# uChameleon.net
KiCad netlist of a schematic drawn in EasyEDA Pro
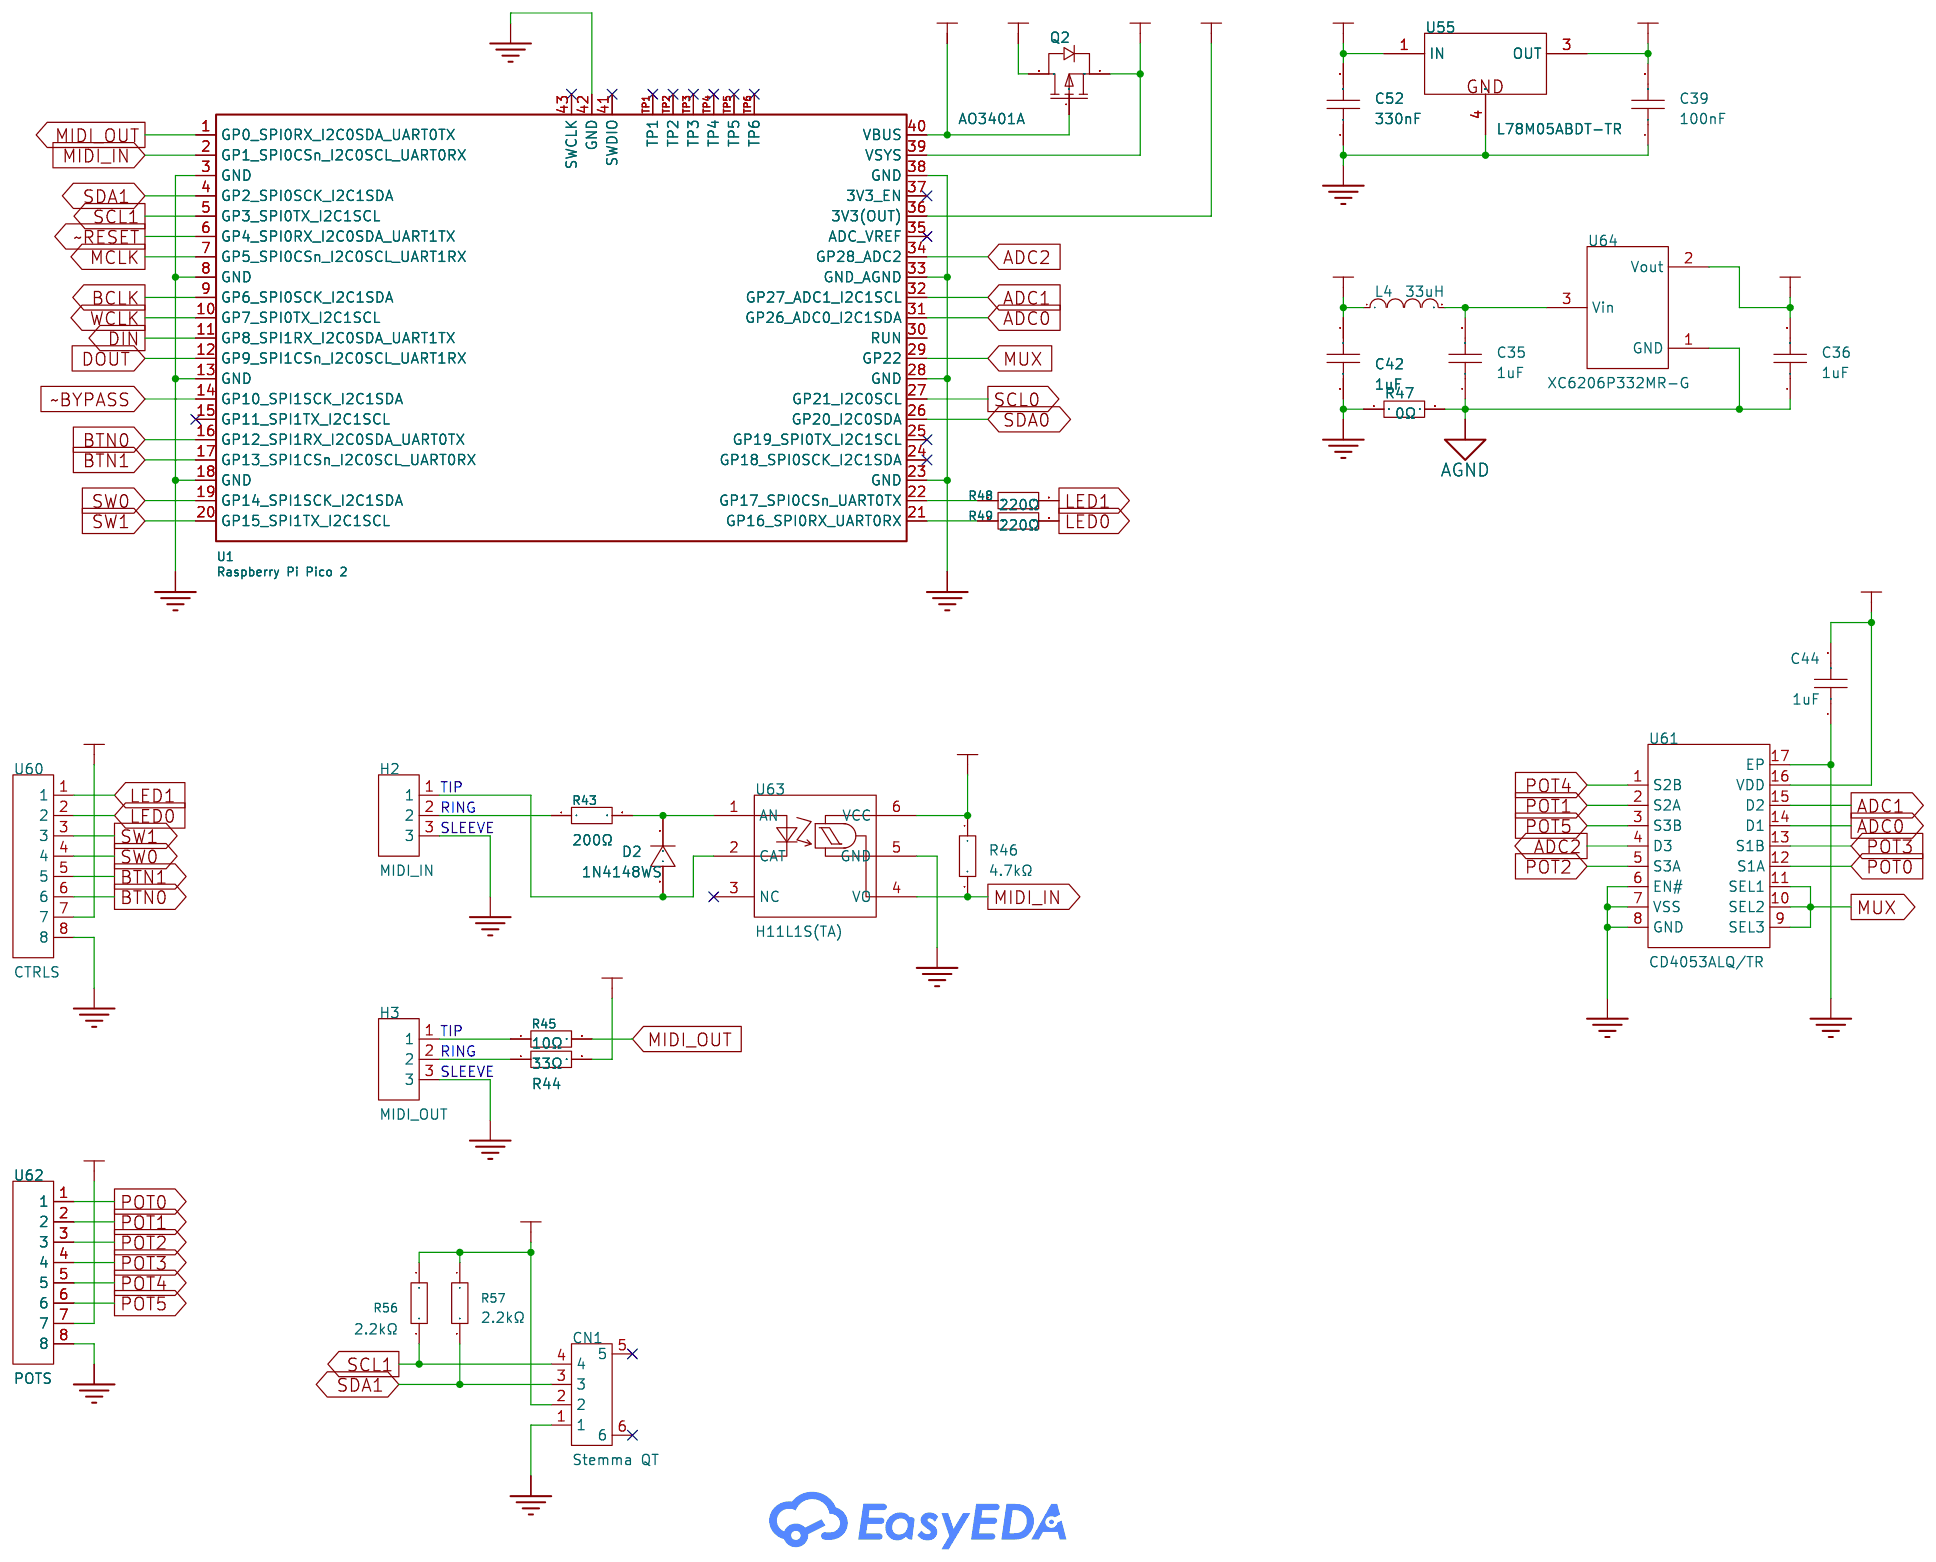
[diagram p0: Pico]
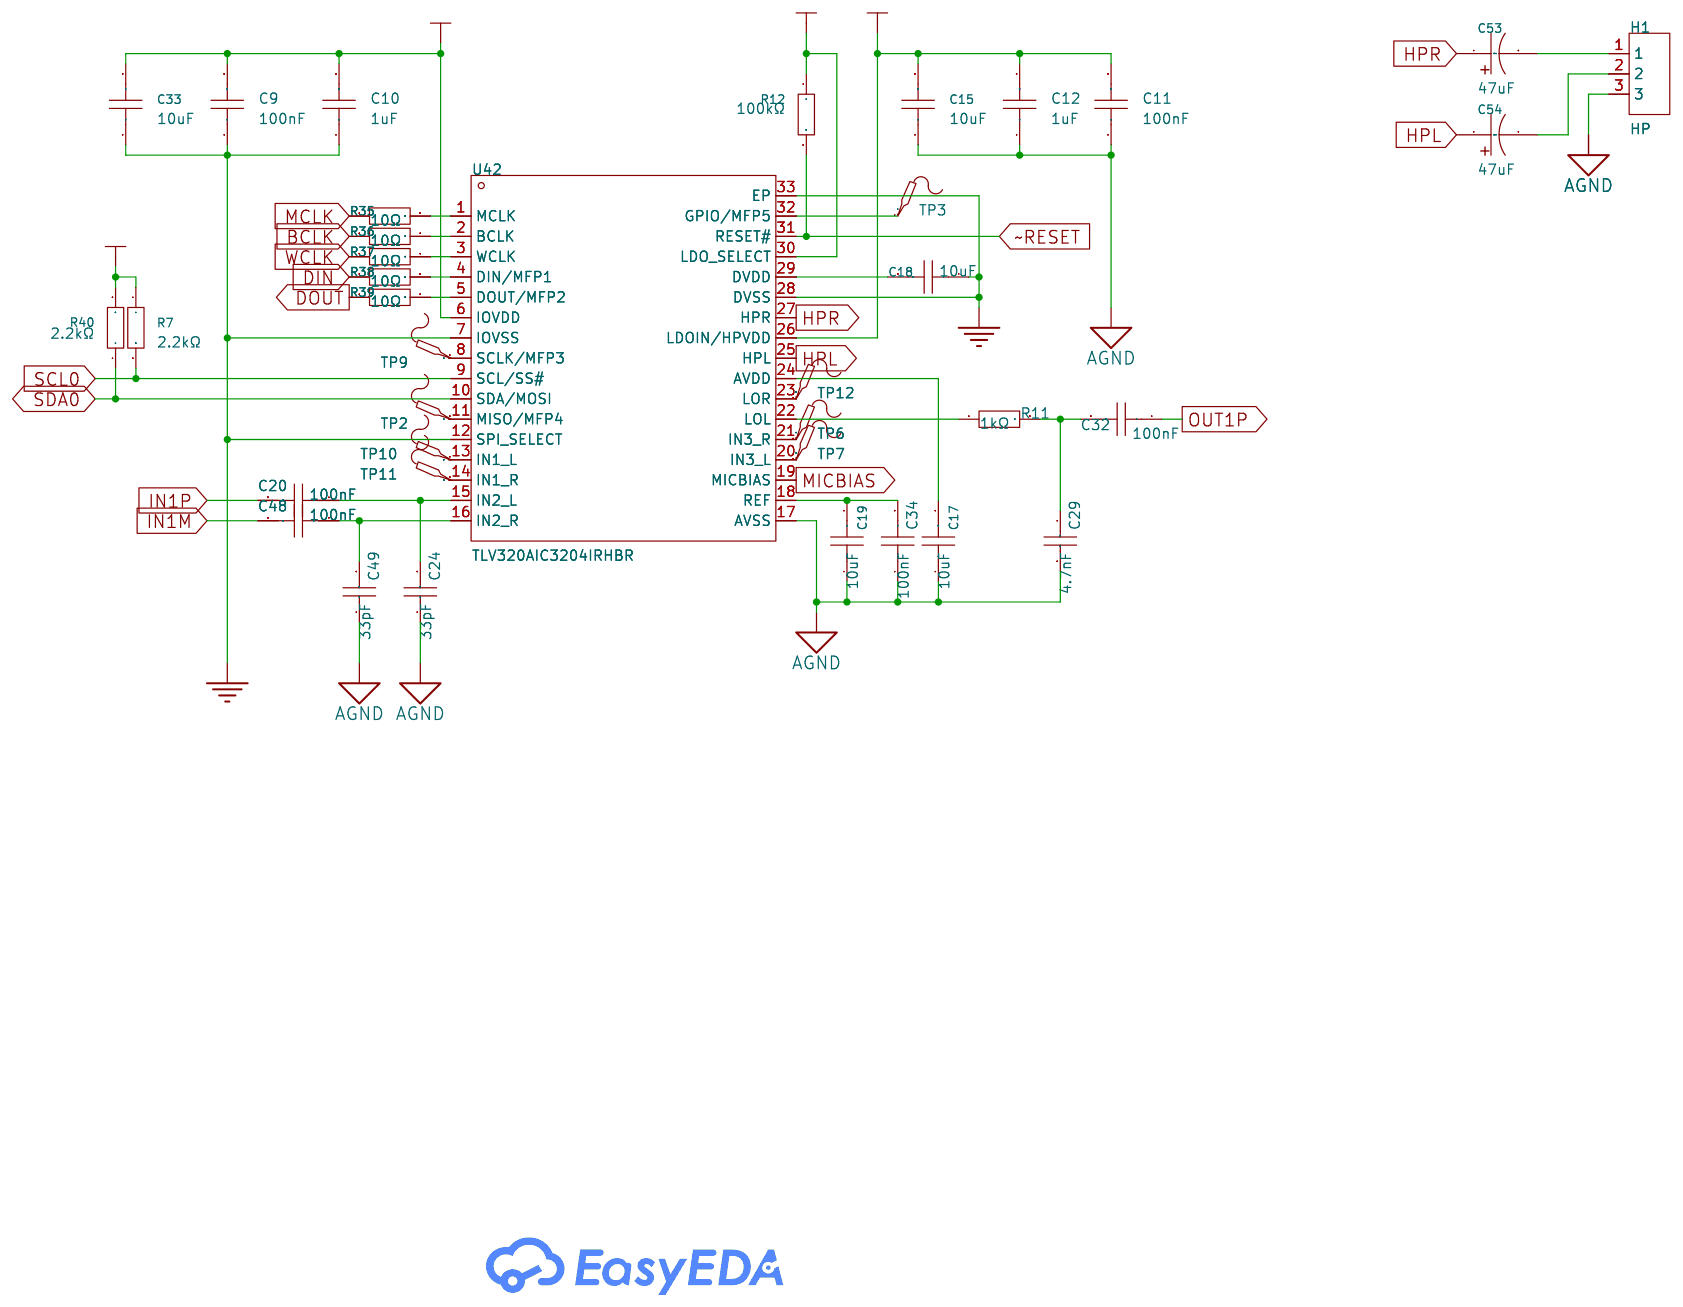
[diagram p1: Codec]
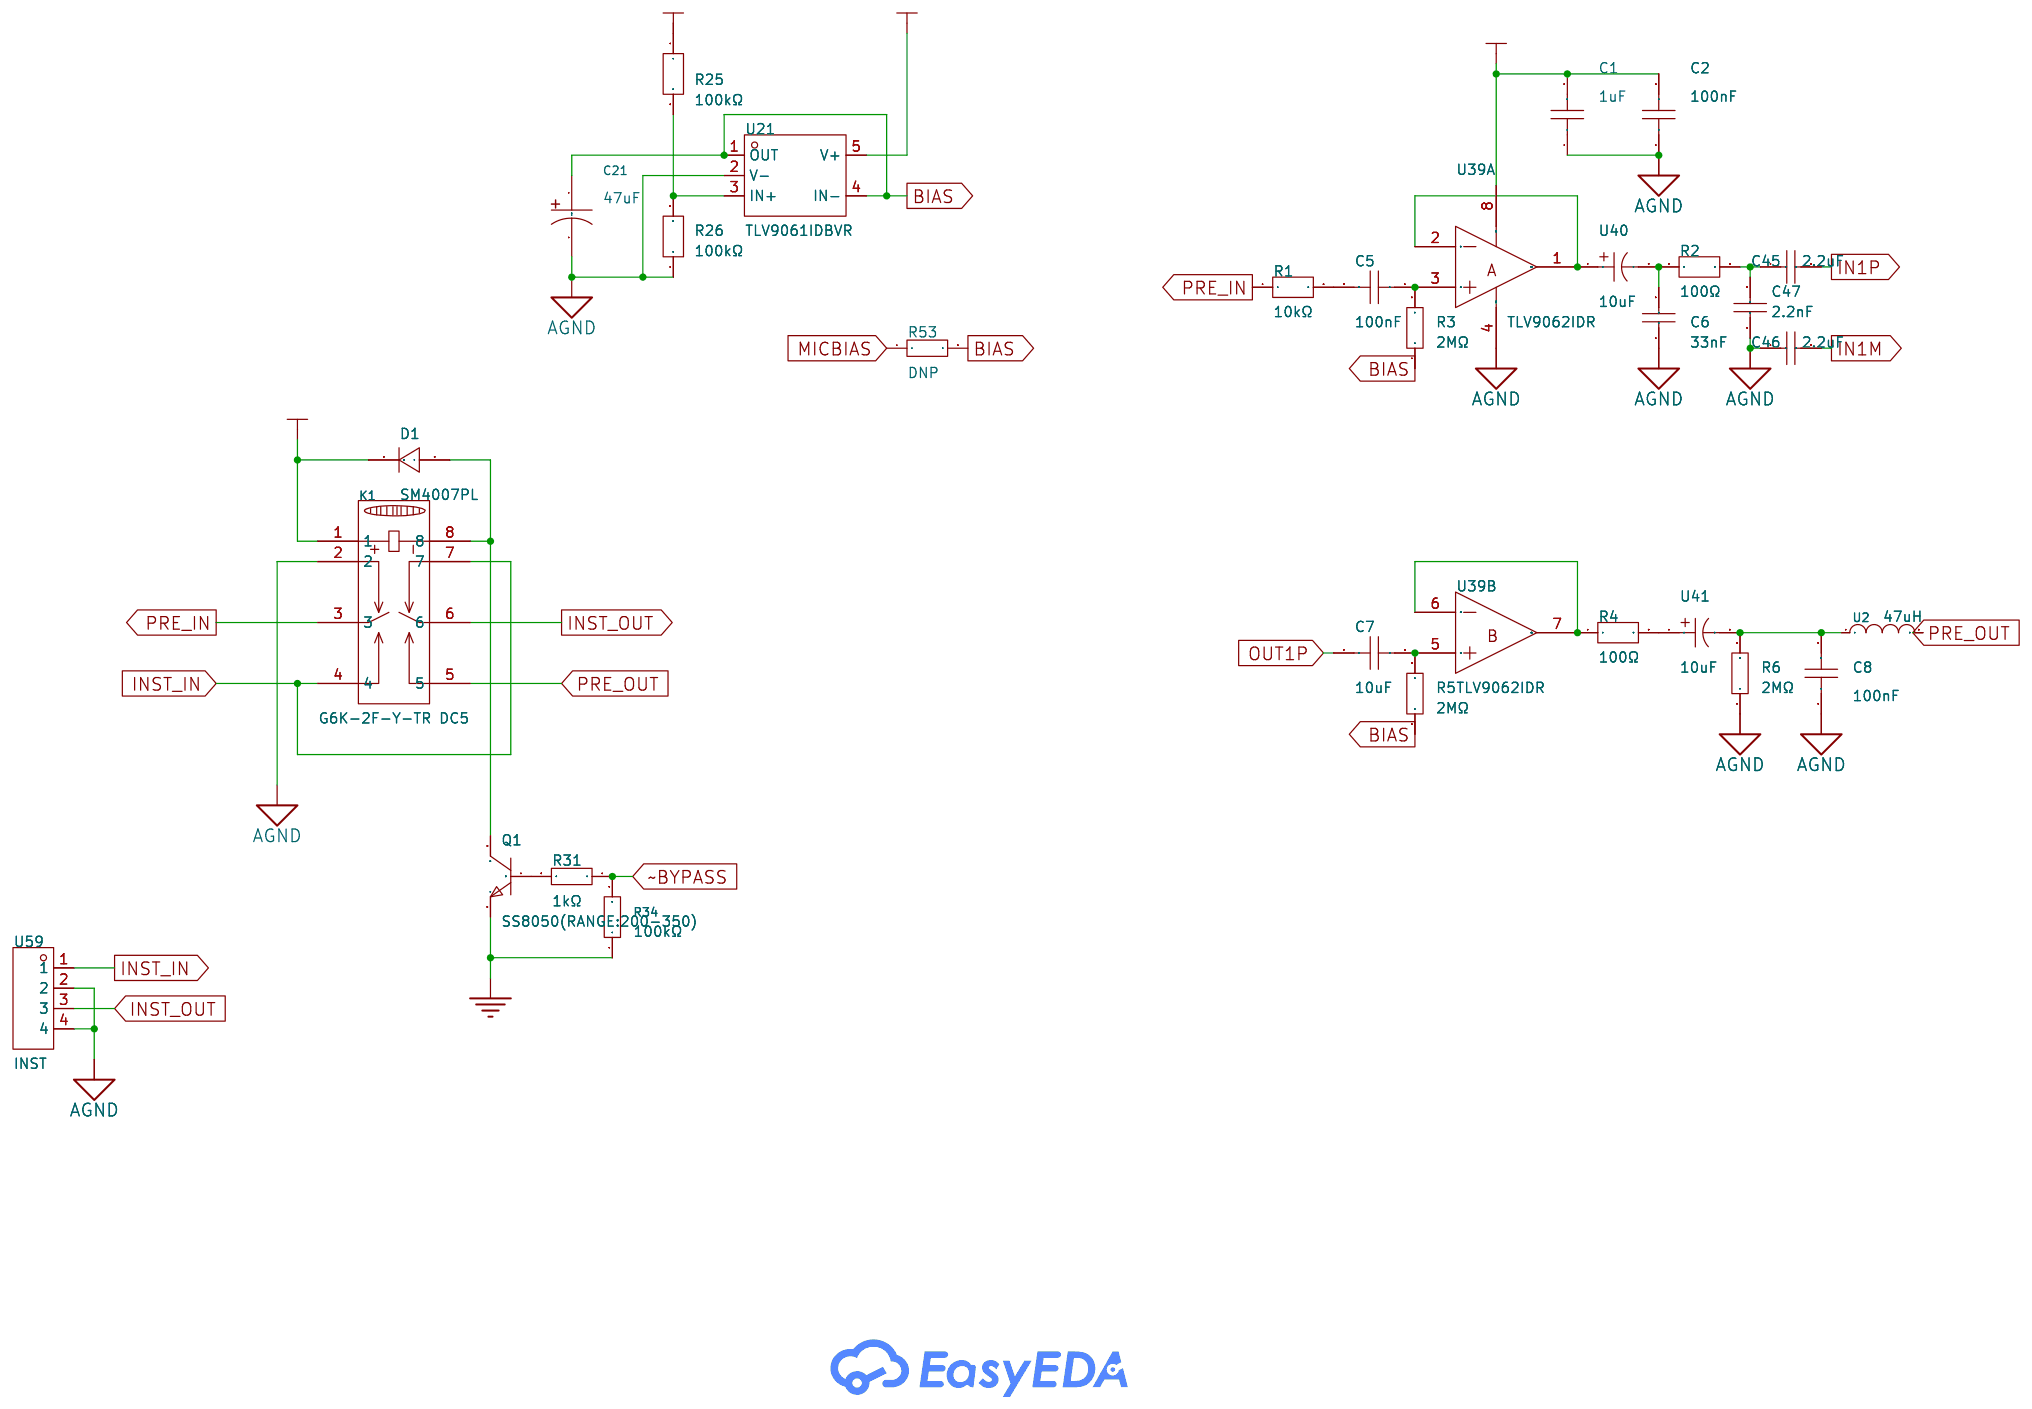
[diagram p2: Preamp]

(export (version "E")
  (design (tool "Eeschema 10.0.6"))
  (components
    (comp (ref "C35")
      (value "1uF")
      (footprint "easyedapro:C0603")
      (description "Capacitance:1uF Tolerance:±10% Tolerance:±10% Voltage Rating:50V Temperature Coefficient:X5R")
      (fields
        (field (name "Manufacturer Part") "CL10A105KB8NNNC")
        (field (name "Manufacturer") "SAMSUNG(三星)")
      )
      (libsource (lib "easyedapro") (part "CL10A105KB8NNNC"))
    )
    (comp (ref "C36")
      (value "1uF")
      (footprint "easyedapro:C0603")
      (description "Capacitance:1uF Tolerance:±10% Tolerance:±10% Voltage Rating:50V Temperature Coefficient:X5R")
      (fields
        (field (name "Manufacturer Part") "CL10A105KB8NNNC")
        (field (name "Manufacturer") "SAMSUNG(三星)")
      )
      (libsource (lib "easyedapro") (part "CL10A105KB8NNNC"))
    )
    (comp (ref "C39")
      (value "100nF")
      (footprint "easyedapro:C0805")
      (description "Capacitance:100nF Tolerance:±10% Tolerance:±10% Voltage Rating:50V Temperature Coefficient:X7R")
      (fields
        (field (name "Manufacturer Part") "CC0805KRX7R9BB104")
        (field (name "Manufacturer") "YAGEO(国巨)")
      )
      (libsource (lib "easyedapro") (part "CC0805KRX7R9BB104"))
    )
    (comp (ref "C42")
      (value "1uF")
      (footprint "easyedapro:C0603")
      (description "Capacitance:1uF Tolerance:±10% Tolerance:±10% Voltage Rating:50V Temperature Coefficient:X5R")
      (fields
        (field (name "Manufacturer Part") "CL10A105KB8NNNC")
        (field (name "Manufacturer") "SAMSUNG(三星)")
      )
      (libsource (lib "easyedapro") (part "CL10A105KB8NNNC"))
    )
    (comp (ref "C44")
      (value "1uF")
      (footprint "easyedapro:C0603")
      (description "Capacitance:1uF Tolerance:±10% Tolerance:±10% Voltage Rating:50V Temperature Coefficient:X5R")
      (fields
        (field (name "Manufacturer Part") "CL10A105KB8NNNC")
        (field (name "Manufacturer") "SAMSUNG(三星)")
      )
      (libsource (lib "easyedapro") (part "CL10A105KB8NNNC"))
    )
    (comp (ref "C52")
      (value "330nF")
      (footprint "easyedapro:C0805")
      (description "Capacitance:330nF Tolerance:±10% Tolerance:±10% Voltage Rating:25V Temperature Coefficient:X7R")
      (fields (field (name "Manufacturer Part") "08053C334K4Z2A") (field (name "Manufacturer") "Kyocera AVX"))
      (libsource (lib "easyedapro") (part "08053C334K4Z2A"))
    )
    (comp (ref "CN1")
      (value "Stemma QT")
      (footprint "easyedapro:CONN-SMD_4P-P1.00_XY-SM04B-SRSS-TB")
      (fields (field (name "Manufacturer") "XYECONN(辛译)"))
      (libsource (lib "easyedapro") (part "XY-SM04B-SRSS-TB"))
    )
    (comp (ref "D2")
      (value "1N4148WS")
      (footprint "easyedapro:SOD-323_L1.8-W1.3-LS2.5-RD")
      (fields (field (name "Manufacturer") "CJ(江苏长电/长晶)"))
      (libsource (lib "easyedapro") (part "1N4148WS T4"))
    )
    (comp (ref "H2")
      (value "MIDI_IN")
      (footprint "easyedapro:HDR-TH_3P-P2.54-V-M")
      (libsource (lib "easyedapro") (part "PZ254V-11-03P_C2937625"))
    )
    (comp (ref "H3")
      (value "MIDI_OUT")
      (footprint "easyedapro:HDR-TH_3P-P2.54-V-M")
      (libsource (lib "easyedapro") (part "PZ254V-11-03P_C2937625"))
    )
    (comp (ref "L4")
      (value "33uH")
      (footprint "easyedapro:IND-SMD_L3.1-W3.1")
      (fields
        (field (name "Manufacturer Part") "SQH3010S-330M-LF")
        (field (name "Manufacturer") "Coilmaster(统宇电研)")
      )
      (libsource (lib "easyedapro") (part "SQH3010S-330M-LF"))
    )
    (comp (ref "Q2")
      (value "AO3401A")
      (footprint "easyedapro:SOT-23-3_L2.9-W1.3-P0.95-LS2.4-BR-1")
      (fields (field (name "Manufacturer") "AOS"))
      (libsource (lib "easyedapro") (part "DMG2305UX"))
    )
    (comp (ref "R43")
      (value "200Ω")
      (footprint "easyedapro:R0402")
      (fields
        (field (name "Manufacturer Part") "0402WGF2000TCE")
        (field (name "Manufacturer") "UNI-ROYAL(厚声)")
      )
      (libsource (lib "easyedapro") (part "0402WGF2000TCE"))
    )
    (comp (ref "R44")
      (value "33Ω")
      (footprint "easyedapro:R0603")
      (fields
        (field (name "Manufacturer Part") "0603WAF330JT5E")
        (field (name "Manufacturer") "UNI-ROYAL(厚声)")
      )
      (libsource (lib "easyedapro") (part "0603WAF330JT5E"))
    )
    (comp (ref "R45")
      (value "10Ω")
      (footprint "easyedapro:R0603")
      (fields
        (field (name "Manufacturer Part") "0603WAF100JT5E")
        (field (name "Manufacturer") "UNI-ROYAL(厚声)")
      )
      (libsource (lib "easyedapro") (part "0603WAF100JT5E"))
    )
    (comp (ref "R46")
      (value "4.7kΩ")
      (footprint "easyedapro:R0603")
      (fields
        (field (name "Manufacturer Part") "0603WAF4701T5E")
        (field (name "Manufacturer") "UNI-ROYAL(厚声)")
      )
      (libsource (lib "easyedapro") (part "0603WAF4701T5E"))
    )
    (comp (ref "R47")
      (value "0Ω")
      (footprint "easyedapro:R0603")
      (fields
        (field (name "Manufacturer Part") "0603WAF0000T5E")
        (field (name "Manufacturer") "UNI-ROYAL(厚声)")
      )
      (libsource (lib "easyedapro") (part "0603WAF0000T5E"))
    )
    (comp (ref "R48")
      (value "220Ω")
      (footprint "easyedapro:R0402")
      (fields
        (field (name "Manufacturer Part") "0402WGF2200TCE")
        (field (name "Manufacturer") "UNI-ROYAL(厚声)")
      )
      (libsource (lib "easyedapro") (part "0402WGF2200TCE"))
    )
    (comp (ref "R49")
      (value "220Ω")
      (footprint "easyedapro:R0402")
      (fields
        (field (name "Manufacturer Part") "0402WGF2200TCE")
        (field (name "Manufacturer") "UNI-ROYAL(厚声)")
      )
      (libsource (lib "easyedapro") (part "0402WGF2200TCE"))
    )
    (comp (ref "R56")
      (value "2.2kΩ")
      (footprint "easyedapro:R0402")
      (fields
        (field (name "Manufacturer Part") "0402WGF2201TCE")
        (field (name "Manufacturer") "UNI-ROYAL(厚声)")
      )
      (libsource (lib "easyedapro") (part "0402WGF2201TCE"))
    )
    (comp (ref "R57")
      (value "2.2kΩ")
      (footprint "easyedapro:R0402")
      (fields
        (field (name "Manufacturer Part") "0402WGF2201TCE")
        (field (name "Manufacturer") "UNI-ROYAL(厚声)")
      )
      (libsource (lib "easyedapro") (part "0402WGF2201TCE"))
    )
    (comp (ref "U1")
      (value "Raspberry Pi Pico 2")
      (footprint "easyedapro:COMM-SMD_L51.0-W21.0-P2.54_SC0916")
      (fields (field (name "Manufacturer") "Raspberry Pi(树莓派)"))
      (libsource (lib "easyedapro") (part "PICO 2"))
    )
    (comp (ref "U55")
      (value "L78M05ABDT-TR")
      (footprint "easyedapro:TO-252-2_L6.5-W6.1-P4.58-LS10.0-TL")
      (fields (field (name "Manufacturer") "ST(意法半导体)"))
      (libsource (lib "easyedapro") (part "L78M05ABDT-TR"))
    )
    (comp (ref "U60")
      (value "CTRLS")
      (footprint "easyedapro:CONN-TH_8P-P3.50_DORABO_DB125-3.5-8P-GN-S")
      (fields (field (name "Manufacturer") "DORABO(地博电气)"))
      (libsource (lib "easyedapro") (part "DB125-3.5-8P-GN-S"))
    )
    (comp (ref "U61")
      (value "CD4053ALQ/TR")
      (footprint "easyedapro:QFN-16_L3.0-W3.0-P0.50-TL-EP1.7-A")
      (fields (field (name "Manufacturer") "HGSEMI(华冠)"))
      (libsource (lib "easyedapro") (part "CD4053ALQ/TR"))
    )
    (comp (ref "U62")
      (value "POTS")
      (footprint "easyedapro:CONN-TH_8P-P3.50_DORABO_DB125-3.5-8P-GN-S")
      (fields (field (name "Manufacturer") "DORABO(地博电气)"))
      (libsource (lib "easyedapro") (part "DB125-3.5-8P-GN-S"))
    )
    (comp (ref "U63")
      (value "H11L1S(TA)")
      (footprint "easyedapro:SMD-6_L7.3-W6.5-P2.54-LS10.2-BL")
      (fields (field (name "Manufacturer") "EVERLIGHT(亿光)"))
      (libsource (lib "easyedapro") (part "H11L1S(TA)"))
    )
    (comp (ref "U64")
      (value "XC6206P332MR-G")
      (footprint "easyedapro:SOT-23-3_L2.9-W1.6-P1.90-LS2.8-BR")
      (fields (field (name "Manufacturer") "TOREX(特瑞仕)"))
      (libsource (lib "easyedapro") (part "XC6206P332MR"))
    )
    (comp (ref "C9")
      (value "100nF")
      (footprint "easyedapro:C0603")
      (description "Capacitance:100nF Tolerance:±10% Tolerance:±10% Voltage Rating:50V Temperature Coefficient:X7R")
      (fields
        (field (name "Manufacturer Part") "CC0603KRX7R9BB104")
        (field (name "Manufacturer") "YAGEO(国巨)")
      )
      (libsource (lib "easyedapro") (part "CC0603KRX7R9BB104"))
    )
    (comp (ref "C10")
      (value "1uF")
      (footprint "easyedapro:C0603")
      (description "Capacitance:1uF Tolerance:±10% Tolerance:±10% Voltage Rating:50V Temperature Coefficient:X5R")
      (fields
        (field (name "Manufacturer Part") "CL10A105KB8NNNC")
        (field (name "Manufacturer") "SAMSUNG(三星)")
      )
      (libsource (lib "easyedapro") (part "CL10A105KB8NNNC"))
    )
    (comp (ref "C11")
      (value "100nF")
      (footprint "easyedapro:C0603")
      (description "Capacitance:100nF Tolerance:±10% Tolerance:±10% Voltage Rating:50V Temperature Coefficient:X7R")
      (fields
        (field (name "Manufacturer Part") "CC0603KRX7R9BB104")
        (field (name "Manufacturer") "YAGEO(国巨)")
      )
      (libsource (lib "easyedapro") (part "CC0603KRX7R9BB104"))
    )
    (comp (ref "C12")
      (value "1uF")
      (footprint "easyedapro:C0603")
      (description "Capacitance:1uF Tolerance:±10% Tolerance:±10% Voltage Rating:50V Temperature Coefficient:X5R")
      (fields
        (field (name "Manufacturer Part") "CL10A105KB8NNNC")
        (field (name "Manufacturer") "SAMSUNG(三星)")
      )
      (libsource (lib "easyedapro") (part "CL10A105KB8NNNC"))
    )
    (comp (ref "C15")
      (value "10uF")
      (footprint "easyedapro:C0603")
      (description "Capacitance:10uF Tolerance:±20% Tolerance:±20% Voltage Rating:25V Temperature Coefficient:X5R")
      (fields
        (field (name "Manufacturer Part") "CL10A106MA8NRNC")
        (field (name "Manufacturer") "SAMSUNG(三星)")
      )
      (libsource (lib "easyedapro") (part "CL10A106MA8NRNC"))
    )
    (comp (ref "C17")
      (value "10uF")
      (footprint "easyedapro:C0603")
      (description "Capacitance:10uF Tolerance:±20% Tolerance:±20% Voltage Rating:25V Temperature Coefficient:X5R")
      (fields
        (field (name "Manufacturer Part") "CL10A106MA8NRNC")
        (field (name "Manufacturer") "SAMSUNG(三星)")
      )
      (libsource (lib "easyedapro") (part "CL10A106MA8NRNC"))
    )
    (comp (ref "C18")
      (value "10uF")
      (footprint "easyedapro:C0603")
      (description "Capacitance:10uF Tolerance:±20% Tolerance:±20% Voltage Rating:25V Temperature Coefficient:X5R")
      (fields
        (field (name "Manufacturer Part") "CL10A106MA8NRNC")
        (field (name "Manufacturer") "SAMSUNG(三星)")
      )
      (libsource (lib "easyedapro") (part "CL10A106MA8NRNC"))
    )
    (comp (ref "C19")
      (value "10uF")
      (footprint "easyedapro:C0603")
      (description "Capacitance:10uF Tolerance:±20% Tolerance:±20% Voltage Rating:25V Temperature Coefficient:X5R")
      (fields
        (field (name "Manufacturer Part") "CL10A106MA8NRNC")
        (field (name "Manufacturer") "SAMSUNG(三星)")
      )
      (libsource (lib "easyedapro") (part "CL10A106MA8NRNC"))
    )
    (comp (ref "C20")
      (value "100nF")
      (footprint "easyedapro:C0603")
      (description "Capacitance:100nF Tolerance:±10% Tolerance:±10% Voltage Rating:50V Temperature Coefficient:X7R")
      (fields
        (field (name "Manufacturer Part") "CC0603KRX7R9BB104")
        (field (name "Manufacturer") "YAGEO(国巨)")
      )
      (libsource (lib "easyedapro") (part "CC0603KRX7R9BB104"))
    )
    (comp (ref "C24")
      (value "33pF")
      (footprint "easyedapro:C0402")
      (description "Capacitance:33pF Tolerance:±5% Tolerance:±5% Voltage Rating:50V Temperature Coefficient:C0G")
      (fields (field (name "Manufacturer Part") "0402CG330J500NT") (field (name "Manufacturer") "FH(风华)"))
      (libsource (lib "easyedapro") (part "0402CG330J500NT"))
    )
    (comp (ref "C29")
      (value "4.7nF")
      (footprint "easyedapro:C0402")
      (description "Capacitance:4.7nF Tolerance:±10% Tolerance:±10% Voltage Rating:50V Temperature Coefficient:X7R")
      (fields (field (name "Manufacturer Part") "0402B472K500NT") (field (name "Manufacturer") "FH(风华)"))
      (libsource (lib "easyedapro") (part "0402B472K500NT"))
    )
    (comp (ref "C32")
      (value "100nF")
      (footprint "easyedapro:C0603")
      (description "Capacitance:100nF Tolerance:±10% Tolerance:±10% Voltage Rating:50V Temperature Coefficient:X7R")
      (fields
        (field (name "Manufacturer Part") "CC0603KRX7R9BB104")
        (field (name "Manufacturer") "YAGEO(国巨)")
      )
      (libsource (lib "easyedapro") (part "CC0603KRX7R9BB104"))
    )
    (comp (ref "C33")
      (value "10uF")
      (footprint "easyedapro:C0603")
      (description "Capacitance:10uF Tolerance:±20% Tolerance:±20% Voltage Rating:25V Temperature Coefficient:X5R")
      (fields
        (field (name "Manufacturer Part") "CL10A106MA8NRNC")
        (field (name "Manufacturer") "SAMSUNG(三星)")
      )
      (libsource (lib "easyedapro") (part "CL10A106MA8NRNC"))
    )
    (comp (ref "C34")
      (value "100nF")
      (footprint "easyedapro:C0603")
      (description "Capacitance:100nF Tolerance:±10% Tolerance:±10% Voltage Rating:50V Temperature Coefficient:X7R")
      (fields
        (field (name "Manufacturer Part") "CC0603KRX7R9BB104")
        (field (name "Manufacturer") "YAGEO(国巨)")
      )
      (libsource (lib "easyedapro") (part "CC0603KRX7R9BB104"))
    )
    (comp (ref "C48")
      (value "100nF")
      (footprint "easyedapro:C0603")
      (description "Capacitance:100nF Tolerance:±10% Tolerance:±10% Voltage Rating:50V Temperature Coefficient:X7R")
      (fields
        (field (name "Manufacturer Part") "CC0603KRX7R9BB104")
        (field (name "Manufacturer") "YAGEO(国巨)")
      )
      (libsource (lib "easyedapro") (part "CC0603KRX7R9BB104"))
    )
    (comp (ref "C49")
      (value "33pF")
      (footprint "easyedapro:C0402")
      (description "Capacitance:33pF Tolerance:±5% Tolerance:±5% Voltage Rating:50V Temperature Coefficient:C0G")
      (fields (field (name "Manufacturer Part") "0402CG330J500NT") (field (name "Manufacturer") "FH(风华)"))
      (libsource (lib "easyedapro") (part "0402CG330J500NT"))
    )
    (comp (ref "C53")
      (value "47uF")
      (fields
        (field (name "Manufacturer Part") "EFVH025ADA470M0554")
        (field (name "Manufacturer") "FOLLON(富隆电子)")
      )
      (libsource (lib "easyedapro") (part "EEEHP0J470P"))
    )
    (comp (ref "C54")
      (value "47uF")
      (fields
        (field (name "Manufacturer Part") "EFVH025ADA470M0554")
        (field (name "Manufacturer") "FOLLON(富隆电子)")
      )
      (libsource (lib "easyedapro") (part "EEEHP0J470P"))
    )
    (comp (ref "H1")
      (value "HP")
      (footprint "easyedapro:HDR-TH_3P-P2.54-V-M")
      (libsource (lib "easyedapro") (part "PZ254V-11-03P_C2937625"))
    )
    (comp (ref "R7")
      (value "2.2kΩ")
      (footprint "easyedapro:R0402")
      (fields
        (field (name "Manufacturer Part") "0402WGF2201TCE")
        (field (name "Manufacturer") "UNI-ROYAL(厚声)")
      )
      (libsource (lib "easyedapro") (part "0402WGF2201TCE"))
    )
    (comp (ref "R11")
      (value "1kΩ")
      (footprint "easyedapro:R0402")
      (fields
        (field (name "Manufacturer Part") "0402WGF1001TCE")
        (field (name "Manufacturer") "UNI-ROYAL(厚声)")
      )
      (libsource (lib "easyedapro") (part "0402WGF1001TCE"))
    )
    (comp (ref "R12")
      (value "100kΩ")
      (footprint "easyedapro:R0402")
      (fields
        (field (name "Manufacturer Part") "0402WGF1003TCE")
        (field (name "Manufacturer") "UNI-ROYAL(厚声)")
      )
      (libsource (lib "easyedapro") (part "0402WGF1003TCE"))
    )
    (comp (ref "R35")
      (value "10Ω")
      (footprint "easyedapro:R0402")
      (fields
        (field (name "Manufacturer Part") "0402WGF100JTCE")
        (field (name "Manufacturer") "UNI-ROYAL(厚声)")
      )
      (libsource (lib "easyedapro") (part "0402WGF100JTCE"))
    )
    (comp (ref "R36")
      (value "10Ω")
      (footprint "easyedapro:R0402")
      (fields
        (field (name "Manufacturer Part") "0402WGF100JTCE")
        (field (name "Manufacturer") "UNI-ROYAL(厚声)")
      )
      (libsource (lib "easyedapro") (part "0402WGF100JTCE"))
    )
    (comp (ref "R37")
      (value "10Ω")
      (footprint "easyedapro:R0402")
      (fields
        (field (name "Manufacturer Part") "0402WGF100JTCE")
        (field (name "Manufacturer") "UNI-ROYAL(厚声)")
      )
      (libsource (lib "easyedapro") (part "0402WGF100JTCE"))
    )
    (comp (ref "R38")
      (value "10Ω")
      (footprint "easyedapro:R0402")
      (fields
        (field (name "Manufacturer Part") "0402WGF100JTCE")
        (field (name "Manufacturer") "UNI-ROYAL(厚声)")
      )
      (libsource (lib "easyedapro") (part "0402WGF100JTCE"))
    )
    (comp (ref "R39")
      (value "10Ω")
      (footprint "easyedapro:R0402")
      (fields
        (field (name "Manufacturer Part") "0402WGF100JTCE")
        (field (name "Manufacturer") "UNI-ROYAL(厚声)")
      )
      (libsource (lib "easyedapro") (part "0402WGF100JTCE"))
    )
    (comp (ref "R40")
      (value "2.2kΩ")
      (footprint "easyedapro:R0402")
      (fields
        (field (name "Manufacturer Part") "0402WGF2201TCE")
        (field (name "Manufacturer") "UNI-ROYAL(厚声)")
      )
      (libsource (lib "easyedapro") (part "0402WGF2201TCE"))
    )
    (comp (ref "TP2")
      (value "~")
      (footprint "easyedapro:Test-Point-0.5mm")
      (description "Test Point 测试点")
      (libsource (lib "easyedapro") (part "Test-Point"))
    )
    (comp (ref "TP3")
      (value "~")
      (footprint "easyedapro:Test-Point-0.5mm")
      (description "Test Point 测试点")
      (libsource (lib "easyedapro") (part "Test-Point"))
    )
    (comp (ref "TP6")
      (value "~")
      (footprint "easyedapro:Test-Point-0.5mm")
      (description "Test Point 测试点")
      (libsource (lib "easyedapro") (part "Test-Point"))
    )
    (comp (ref "TP7")
      (value "~")
      (footprint "easyedapro:Test-Point-0.5mm")
      (description "Test Point 测试点")
      (libsource (lib "easyedapro") (part "Test-Point"))
    )
    (comp (ref "TP9")
      (value "~")
      (footprint "easyedapro:Test-Point-0.5mm")
      (description "Test Point 测试点")
      (libsource (lib "easyedapro") (part "Test-Point"))
    )
    (comp (ref "TP10")
      (value "~")
      (footprint "easyedapro:Test-Point-0.5mm")
      (description "Test Point 测试点")
      (libsource (lib "easyedapro") (part "Test-Point"))
    )
    (comp (ref "TP11")
      (value "~")
      (footprint "easyedapro:Test-Point-0.5mm")
      (description "Test Point 测试点")
      (libsource (lib "easyedapro") (part "Test-Point"))
    )
    (comp (ref "TP12")
      (value "~")
      (footprint "easyedapro:Test-Point-0.5mm")
      (description "Test Point 测试点")
      (libsource (lib "easyedapro") (part "Test-Point"))
    )
    (comp (ref "U42")
      (value "TLV320AIC3204IRHBR")
      (footprint "easyedapro:QFN-32_L5.0-W5.0-P0.50-TL-EP3.4")
      (fields (field (name "Manufacturer") "TI(德州仪器)"))
      (libsource (lib "easyedapro") (part "TLV320AIC3204IRHBR"))
    )
    (comp (ref "C1")
      (value "1uF")
      (fields
        (field (name "Manufacturer Part") "CL10A105KB8NNNC")
        (field (name "Manufacturer") "SAMSUNG(三星)")
      )
      (libsource (lib "easyedapro") (part "CT41G-0805-2X1-50V-1μF-K(N)"))
    )
    (comp (ref "C2")
      (value "100nF")
      (footprint "easyedapro:C0402")
      (description "Capacitance:100nF Tolerance:±10% Tolerance:±10% Voltage Rating:16V Temperature Coefficient:-")
      (fields
        (field (name "Manufacturer Part") "CL05B104KO5NNNC")
        (field (name "Manufacturer") "SAMSUNG(三星)")
      )
      (libsource (lib "easyedapro") (part "CT41G-0402-2X1-16V-0.1μF-K(N)"))
    )
    (comp (ref "C5")
      (value "100nF")
      (footprint "easyedapro:C0402")
      (description "Capacitance:100nF Tolerance:±10% Tolerance:±10% Voltage Rating:16V Temperature Coefficient:-")
      (fields
        (field (name "Manufacturer Part") "CL05B104KO5NNNC")
        (field (name "Manufacturer") "SAMSUNG(三星)")
      )
      (libsource (lib "easyedapro") (part "CT41G-0402-2X1-16V-0.1μF-K(N)"))
    )
    (comp (ref "C6")
      (value "33nF")
      (footprint "easyedapro:C0603")
      (description "Capacitance:33nF Tolerance:±10% Tolerance:±10% Voltage Rating:50V Temperature Coefficient:X7R")
      (fields
        (field (name "Manufacturer Part") "CL10B333KB8NNNC")
        (field (name "Manufacturer") "SAMSUNG(三星)")
      )
      (libsource (lib "easyedapro") (part "CL10B333KB8NNNC"))
    )
    (comp (ref "C7")
      (value "10uF")
      (description "Capacitance:10uF Tolerance:±20% Tolerance:±20% Voltage Rating:25V Temperature Coefficient:X5R")
      (fields
        (field (name "Manufacturer Part") "CL10A106MA8NRNC")
        (field (name "Manufacturer") "SAMSUNG(三星)")
      )
      (libsource (lib "easyedapro") (part "CL21A106KAYNNNE"))
    )
    (comp (ref "C8")
      (value "100nF")
      (footprint "easyedapro:C0402")
      (description "Capacitance:100nF Tolerance:±10% Tolerance:±10% Voltage Rating:16V Temperature Coefficient:-")
      (fields
        (field (name "Manufacturer Part") "CL05B104KO5NNNC")
        (field (name "Manufacturer") "SAMSUNG(三星)")
      )
      (libsource (lib "easyedapro") (part "CT41G-0402-2X1-16V-0.1μF-K(N)"))
    )
    (comp (ref "C21")
      (value "47uF")
      (fields
        (field (name "Manufacturer Part") "EFVH025ADA470M0554")
        (field (name "Manufacturer") "FOLLON(富隆电子)")
      )
      (libsource (lib "easyedapro") (part "EEEHP0J470P"))
    )
    (comp (ref "C45")
      (value "2.2uF")
      (footprint "easyedapro:C0603")
      (description "Capacitance:2.2uF Tolerance:±10% Tolerance:±10% Voltage Rating:16V Temperature Coefficient:X5R")
      (fields
        (field (name "Manufacturer Part") "CL10A225KO8NNNC")
        (field (name "Manufacturer") "SAMSUNG(三星)")
      )
      (libsource (lib "easyedapro") (part "CL10A225KO8NNNC"))
    )
    (comp (ref "C46")
      (value "2.2uF")
      (footprint "easyedapro:C0603")
      (description "Capacitance:2.2uF Tolerance:±10% Tolerance:±10% Voltage Rating:16V Temperature Coefficient:X5R")
      (fields
        (field (name "Manufacturer Part") "CL10A225KO8NNNC")
        (field (name "Manufacturer") "SAMSUNG(三星)")
      )
      (libsource (lib "easyedapro") (part "CL10A225KO8NNNC"))
    )
    (comp (ref "C47")
      (value "2.2nF")
      (footprint "easyedapro:C0603")
      (description "Capacitance:2.2nF Tolerance:±10% Tolerance:±10% Voltage Rating:50V Temperature Coefficient:X7R")
      (fields (field (name "Manufacturer Part") "0603B222K500NT") (field (name "Manufacturer") "FH(风华)"))
      (libsource (lib "easyedapro") (part "0603B222K500NT"))
    )
    (comp (ref "D1")
      (value "SM4007PL")
      (footprint "easyedapro:SOD-123F_L2.8-W1.8-LS3.7-RD")
      (fields (field (name "Manufacturer") "MDD(辰达半导体)"))
      (libsource (lib "easyedapro") (part "SM4007PL"))
    )
    (comp (ref "K1")
      (value "G6K-2F-Y-TR DC5")
      (footprint "easyedapro:RELAY-SMD_G6K-2F-X-XX")
      (fields (field (name "Manufacturer") "OMRON(欧姆龙)"))
      (libsource (lib "easyedapro") (part "G6K-2F-Y-DC5"))
    )
    (comp (ref "Q1")
      (value "SS8050(RANGE:200-350)")
      (footprint "easyedapro:SOT-23-3_L3.0-W1.3-P1.90-LS2.5-BR")
      (fields (field (name "Manufacturer") "CJ(江苏长电/长晶)"))
      (libsource (lib "easyedapro") (part "SS8050_C181160"))
    )
    (comp (ref "R1")
      (value "10kΩ")
      (footprint "easyedapro:R0603")
      (fields
        (field (name "Manufacturer Part") "0603WAF1002T5E")
        (field (name "Manufacturer") "UNI-ROYAL(厚声)")
      )
      (libsource (lib "easyedapro") (part "AC0603JR-1310KL"))
    )
    (comp (ref "R2")
      (value "100Ω")
      (footprint "easyedapro:R0603")
      (fields
        (field (name "Manufacturer Part") "0603WAF1000T5E")
        (field (name "Manufacturer") "UNI-ROYAL(厚声)")
      )
      (libsource (lib "easyedapro") (part "RT0603FRE07100RL"))
    )
    (comp (ref "R3")
      (value "2MΩ")
      (fields
        (field (name "Manufacturer Part") "0603WAF2004T5E")
        (field (name "Manufacturer") "UNI-ROYAL(厚声)")
      )
      (libsource (lib "easyedapro") (part "RC0603FR-072ML"))
    )
    (comp (ref "R4")
      (value "100Ω")
      (footprint "easyedapro:R0603")
      (fields
        (field (name "Manufacturer Part") "0603WAF1000T5E")
        (field (name "Manufacturer") "UNI-ROYAL(厚声)")
      )
      (libsource (lib "easyedapro") (part "RT0603FRE07100RL"))
    )
    (comp (ref "R5")
      (value "2MΩ")
      (fields
        (field (name "Manufacturer Part") "0603WAF2004T5E")
        (field (name "Manufacturer") "UNI-ROYAL(厚声)")
      )
      (libsource (lib "easyedapro") (part "RC0603FR-072ML"))
    )
    (comp (ref "R6")
      (value "2MΩ")
      (fields
        (field (name "Manufacturer Part") "0603WAF2004T5E")
        (field (name "Manufacturer") "UNI-ROYAL(厚声)")
      )
      (libsource (lib "easyedapro") (part "RC0603FR-072ML"))
    )
    (comp (ref "R25")
      (value "100kΩ")
      (fields
        (field (name "Manufacturer Part") "0402WGF1003TCE")
        (field (name "Manufacturer") "UNI-ROYAL(厚声)")
      )
      (libsource (lib "easyedapro") (part "RT0603FRE07100KL"))
    )
    (comp (ref "R26")
      (value "100kΩ")
      (fields
        (field (name "Manufacturer Part") "0402WGF1003TCE")
        (field (name "Manufacturer") "UNI-ROYAL(厚声)")
      )
      (libsource (lib "easyedapro") (part "RT0603FRE07100KL"))
    )
    (comp (ref "R31")
      (value "1kΩ")
      (footprint "easyedapro:R0402")
      (fields
        (field (name "Manufacturer Part") "0402WGF1001TCE")
        (field (name "Manufacturer") "UNI-ROYAL(厚声)")
      )
      (libsource (lib "easyedapro") (part "RC0402JR-071KL"))
    )
    (comp (ref "R34")
      (value "100kΩ")
      (footprint "easyedapro:R0402")
      (fields
        (field (name "Manufacturer Part") "0402WGF1003TCE")
        (field (name "Manufacturer") "UNI-ROYAL(厚声)")
      )
      (libsource (lib "easyedapro") (part "0402WGF1003TCE"))
    )
    (comp (ref "R53")
      (value "DNP")
      (footprint "easyedapro:R0805")
      (libsource (lib "easyedapro") (part "Res"))
    )
    (comp (ref "U2")
      (value "47uH")
      (footprint "easyedapro:IND-SMD_L3.0-W3.0-HPC3015TF-2R2M")
      (description "Inductance: Tolerance:±20% Tolerance:±20%")
      (fields (field (name "Manufacturer Part") "SNR3015TYD470M") (field (name "Manufacturer") "SOREDE(索瑞达)"))
      (libsource (lib "easyedapro") (part "SNR3015TYD470M"))
    )
    (comp (ref "U21")
      (value "TLV9061IDBVR")
      (footprint "easyedapro:SOT-23-5_L3.0-W1.7-P0.95-LS2.8-BL")
      (fields (field (name "Manufacturer") "TI(德州仪器)"))
      (libsource (lib "easyedapro") (part "TLV9061IDBVR"))
    )
    (comp (ref "U39")
      (value "TLV9062IDR")
      (footprint "easyedapro:SOIC-8_L5.0-W4.0-P1.27-LS6.0-BL")
      (fields (field (name "Manufacturer") "TI(德州仪器)"))
      (libsource (lib "easyedapro") (part "TLV9062IDR"))
    )
    (comp (ref "U40")
      (value "10uF")
      (footprint "easyedapro:CAP-SMD_BD4.0-L4.3-W4.3-LS5.0-FD")
      (fields (field (name "Manufacturer Part") "RST10UF35V015") (field (name "Manufacturer") "KNSCHA(科尼盛)"))
      (libsource (lib "easyedapro") (part "RST10UF35V015"))
    )
    (comp (ref "U41")
      (value "10uF")
      (footprint "easyedapro:CAP-SMD_BD4.0-L4.3-W4.3-LS5.0-FD")
      (fields (field (name "Manufacturer Part") "RST10UF35V015") (field (name "Manufacturer") "KNSCHA(科尼盛)"))
      (libsource (lib "easyedapro") (part "RST10UF35V015"))
    )
    (comp (ref "U59")
      (value "INST")
      (footprint "easyedapro:CONN-TH_DB125-3.5-4P-GN")
      (fields (field (name "Manufacturer") "DORABO(地博电气)"))
      (libsource (lib "easyedapro") (part "DB125-3.5-4P-GN"))
    )
  )
  (nets
    (net (code "1") (name "+3.3VA") (class "Default")
      (node (ref "C1") (pin "2") (pinfunction "2_2") (pintype "unspecified"))
      (node (ref "C11") (pin "2") (pinfunction "2_2") (pintype "unspecified"))
      (node (ref "C12") (pin "2") (pinfunction "2_2") (pintype "unspecified"))
      (node (ref "C15") (pin "2") (pinfunction "2_2") (pintype "input"))
      (node (ref "C2") (pin "2") (pinfunction "2_2") (pintype "unspecified"))
      (node (ref "C36") (pin "2") (pinfunction "2_2") (pintype "unspecified"))
      (node (ref "R25") (pin "1") (pinfunction "1_1") (pintype "unspecified"))
      (node (ref "U21") (pin "5") (pinfunction "V+_5") (pintype "unspecified"))
      (node (ref "U39") (pin "8") (pinfunction "VCC_8") (pintype "unspecified"))
      (node (ref "U42") (pin "26") (pinfunction "LDOIN/HPVDD_26") (pintype "unspecified"))
      (node (ref "U64") (pin "2") (pinfunction "Vout_2") (pintype "unspecified"))
    )
    (net (code "2") (name "+3.3VD") (class "Default")
      (node (ref "C10") (pin "2") (pinfunction "2_2") (pintype "unspecified"))
      (node (ref "C33") (pin "2") (pinfunction "2_2") (pintype "input"))
      (node (ref "C44") (pin "2") (pinfunction "2_2") (pintype "unspecified"))
      (node (ref "C9") (pin "2") (pinfunction "2_2") (pintype "unspecified"))
      (node (ref "CN1") (pin "2") (pinfunction "2_2") (pintype "unspecified"))
      (node (ref "R12") (pin "1") (pinfunction "1_1") (pintype "input"))
      (node (ref "R40") (pin "2") (pinfunction "2_2") (pintype "input"))
      (node (ref "R44") (pin "2") (pinfunction "2_2") (pintype "input"))
      (node (ref "R46") (pin "1") (pinfunction "1_1") (pintype "input"))
      (node (ref "R56") (pin "1") (pinfunction "1_1") (pintype "input"))
      (node (ref "R57") (pin "1") (pinfunction "1_1") (pintype "input"))
      (node (ref "R7") (pin "1") (pinfunction "1_1") (pintype "input"))
      (node (ref "U1") (pin "36") (pinfunction "3V3(OUT)_36") (pintype "unspecified"))
      (node (ref "U42") (pin "30") (pinfunction "LDO_SELECT_30") (pintype "unspecified"))
      (node (ref "U42") (pin "6") (pinfunction "IOVDD_6") (pintype "unspecified"))
      (node (ref "U61") (pin "16") (pinfunction "VDD_16") (pintype "unspecified"))
      (node (ref "U62") (pin "7") (pinfunction "7_7") (pintype "unspecified"))
      (node (ref "U63") (pin "6") (pinfunction "VCC_6") (pintype "unspecified"))
    )
    (net (code "3") (name "+5VD") (class "Default")
      (node (ref "C42") (pin "1") (pinfunction "1_1") (pintype "unspecified"))
      (node (ref "D1") (pin "1") (pinfunction "C_1") (pintype "unspecified"))
      (node (ref "K1") (pin "1") (pinfunction "1_1") (pintype "input"))
      (node (ref "L4") (pin "1") (pinfunction "1_1") (pintype "unspecified"))
      (node (ref "Q2") (pin "2") (pinfunction "S_2") (pintype "unspecified"))
      (node (ref "U1") (pin "39") (pinfunction "VSYS_39") (pintype "unspecified"))
    )
    (net (code "4") (name "ADC0") (class "Default")
      (node (ref "U1") (pin "31") (pinfunction "GP26_ADC0_I2C1SDA_31") (pintype "unspecified"))
      (node (ref "U61") (pin "14") (pinfunction "D1_14") (pintype "unspecified"))
    )
    (net (code "5") (name "ADC1") (class "Default")
      (node (ref "U1") (pin "32") (pinfunction "GP27_ADC1_I2C1SCL_32") (pintype "unspecified"))
      (node (ref "U61") (pin "15") (pinfunction "D2_15") (pintype "unspecified"))
    )
    (net (code "6") (name "ADC2") (class "Default")
      (node (ref "U1") (pin "34") (pinfunction "GP28_ADC2_34") (pintype "unspecified"))
      (node (ref "U61") (pin "4") (pinfunction "D3_4") (pintype "unspecified"))
    )
    (net (code "7") (name "AGND") (class "Default")
      (node (ref "C1") (pin "1") (pinfunction "1_1") (pintype "unspecified"))
      (node (ref "C11") (pin "1") (pinfunction "1_1") (pintype "unspecified"))
      (node (ref "C12") (pin "1") (pinfunction "1_1") (pintype "unspecified"))
      (node (ref "C15") (pin "1") (pinfunction "1_1") (pintype "input"))
      (node (ref "C17") (pin "1") (pinfunction "1_1") (pintype "input"))
      (node (ref "C19") (pin "1") (pinfunction "1_1") (pintype "input"))
      (node (ref "C2") (pin "1") (pinfunction "1_1") (pintype "unspecified"))
      (node (ref "C21") (pin "2") (pinfunction "2_2") (pintype "input"))
      (node (ref "C24") (pin "1") (pinfunction "1_1") (pintype "input"))
      (node (ref "C29") (pin "2") (pinfunction "2_2") (pintype "input"))
      (node (ref "C34") (pin "1") (pinfunction "1_1") (pintype "unspecified"))
      (node (ref "C35") (pin "1") (pinfunction "1_1") (pintype "unspecified"))
      (node (ref "C36") (pin "1") (pinfunction "1_1") (pintype "unspecified"))
      (node (ref "C46") (pin "1") (pinfunction "1_1") (pintype "input"))
      (node (ref "C47") (pin "1") (pinfunction "1_1") (pintype "input"))
      (node (ref "C49") (pin "1") (pinfunction "1_1") (pintype "input"))
      (node (ref "C6") (pin "1") (pinfunction "1_1") (pintype "input"))
      (node (ref "C8") (pin "1") (pinfunction "1_1") (pintype "unspecified"))
      (node (ref "H1") (pin "3") (pinfunction "3_3") (pintype "unspecified"))
      (node (ref "K1") (pin "2") (pinfunction "2_2") (pintype "input"))
      (node (ref "R26") (pin "1") (pinfunction "1_1") (pintype "unspecified"))
      (node (ref "R47") (pin "2") (pinfunction "2_2") (pintype "input"))
      (node (ref "R6") (pin "1") (pinfunction "1_1") (pintype "input"))
      (node (ref "U21") (pin "2") (pinfunction "V-_2") (pintype "unspecified"))
      (node (ref "U39") (pin "4") (pinfunction "VEE/GND_4") (pintype "unspecified"))
      (node (ref "U42") (pin "17") (pinfunction "AVSS_17") (pintype "unspecified"))
      (node (ref "U59") (pin "2") (pinfunction "2_2") (pintype "unspecified"))
      (node (ref "U59") (pin "4") (pinfunction "4_4") (pintype "unspecified"))
      (node (ref "U64") (pin "1") (pinfunction "GND_1") (pintype "unspecified"))
    )
    (net (code "8") (name "BCLK") (class "Default")
      (node (ref "R36") (pin "1") (pinfunction "1_1") (pintype "input"))
      (node (ref "U1") (pin "9") (pinfunction "GP6_SPI0SCK_I2C1SDA_9") (pintype "unspecified"))
    )
    (net (code "9") (name "BIAS") (class "Default")
      (node (ref "C21") (pin "1") (pinfunction "1_1") (pintype "input"))
      (node (ref "R3") (pin "1") (pinfunction "1_1") (pintype "input"))
      (node (ref "R5") (pin "1") (pinfunction "1_1") (pintype "input"))
      (node (ref "R53") (pin "2") (pinfunction "2_2") (pintype "input"))
      (node (ref "U21") (pin "1") (pinfunction "OUT_1") (pintype "unspecified"))
      (node (ref "U21") (pin "4") (pinfunction "IN-_4") (pintype "unspecified"))
    )
    (net (code "10") (name "BTN0") (class "Default")
      (node (ref "U1") (pin "16") (pinfunction "GP12_SPI1RX_I2C0SDA_UART0TX_16") (pintype "unspecified"))
      (node (ref "U60") (pin "6") (pinfunction "6_6") (pintype "unspecified"))
    )
    (net (code "11") (name "BTN1") (class "Default")
      (node (ref "U1") (pin "17") (pinfunction "GP13_SPI1CSn_I2C0SCL_UART0RX_17") (pintype "unspecified"))
      (node (ref "U60") (pin "5") (pinfunction "5_5") (pintype "unspecified"))
    )
    (net (code "12") (name "DGND") (class "Default")
      (node (ref "C10") (pin "1") (pinfunction "1_1") (pintype "unspecified"))
      (node (ref "C18") (pin "1") (pinfunction "1_1") (pintype "input"))
      (node (ref "C33") (pin "1") (pinfunction "1_1") (pintype "input"))
      (node (ref "C39") (pin "1") (pinfunction "1_1") (pintype "unspecified"))
      (node (ref "C42") (pin "2") (pinfunction "2_2") (pintype "unspecified"))
      (node (ref "C44") (pin "1") (pinfunction "1_1") (pintype "unspecified"))
      (node (ref "C52") (pin "1") (pinfunction "1_1") (pintype "unspecified"))
      (node (ref "C9") (pin "1") (pinfunction "1_1") (pintype "unspecified"))
      (node (ref "CN1") (pin "1") (pinfunction "1_1") (pintype "unspecified"))
      (node (ref "H2") (pin "3") (pinfunction "3_3") (pintype "unspecified"))
      (node (ref "H3") (pin "3") (pinfunction "3_3") (pintype "unspecified"))
      (node (ref "Q1") (pin "2") (pinfunction "E_2") (pintype "input"))
      (node (ref "R34") (pin "1") (pinfunction "1_1") (pintype "input"))
      (node (ref "R47") (pin "1") (pinfunction "1_1") (pintype "input"))
      (node (ref "U1") (pin "13") (pinfunction "GND_13") (pintype "unspecified"))
      (node (ref "U1") (pin "18") (pinfunction "GND_18") (pintype "unspecified"))
      (node (ref "U1") (pin "23") (pinfunction "GND_23") (pintype "unspecified"))
      (node (ref "U1") (pin "28") (pinfunction "GND_28") (pintype "unspecified"))
      (node (ref "U1") (pin "3") (pinfunction "GND_3") (pintype "unspecified"))
      (node (ref "U1") (pin "33") (pinfunction "GND_AGND_33") (pintype "unspecified"))
      (node (ref "U1") (pin "38") (pinfunction "GND_38") (pintype "unspecified"))
      (node (ref "U1") (pin "42") (pinfunction "GND_42") (pintype "unspecified"))
      (node (ref "U1") (pin "8") (pinfunction "GND_8") (pintype "unspecified"))
      (node (ref "U42") (pin "12") (pinfunction "SPI_SELECT_12") (pintype "unspecified"))
      (node (ref "U42") (pin "28") (pinfunction "DVSS_28") (pintype "unspecified"))
      (node (ref "U42") (pin "33") (pinfunction "EP_33") (pintype "unspecified"))
      (node (ref "U42") (pin "7") (pinfunction "IOVSS_7") (pintype "unspecified"))
      (node (ref "U55") (pin "4") (pinfunction "GND_4") (pintype "unspecified"))
      (node (ref "U60") (pin "8") (pinfunction "8_8") (pintype "unspecified"))
      (node (ref "U61") (pin "17") (pinfunction "EP_17") (pintype "unspecified"))
      (node (ref "U61") (pin "6") (pinfunction "EN#_6") (pintype "unspecified"))
      (node (ref "U61") (pin "7") (pinfunction "VSS_7") (pintype "unspecified"))
      (node (ref "U61") (pin "8") (pinfunction "GND_8") (pintype "unspecified"))
      (node (ref "U62") (pin "8") (pinfunction "8_8") (pintype "unspecified"))
      (node (ref "U63") (pin "5") (pinfunction "GND_5") (pintype "unspecified"))
    )
    (net (code "13") (name "DIN") (class "Default")
      (node (ref "R38") (pin "1") (pinfunction "1_1") (pintype "input"))
      (node (ref "U1") (pin "11") (pinfunction "GP8_SPI1RX_I2C0SDA_UART1TX_11") (pintype "unspecified"))
    )
    (net (code "14") (name "DOUT") (class "Default")
      (node (ref "R39") (pin "1") (pinfunction "1_1") (pintype "input"))
      (node (ref "U1") (pin "12") (pinfunction "GP9_SPI1CSn_I2C0SCL_UART1RX_12") (pintype "unspecified"))
    )
    (net (code "15") (name "HPL") (class "Default")
      (node (ref "C54") (pin "1") (pinfunction "1_1") (pintype "input"))
      (node (ref "U42") (pin "25") (pinfunction "HPL_25") (pintype "unspecified"))
    )
    (net (code "16") (name "HPR") (class "Default")
      (node (ref "C53") (pin "1") (pinfunction "1_1") (pintype "input"))
      (node (ref "U42") (pin "27") (pinfunction "HPR_27") (pintype "unspecified"))
    )
    (net (code "17") (name "IN1M") (class "Default")
      (node (ref "C46") (pin "2") (pinfunction "2_2") (pintype "input"))
      (node (ref "C48") (pin "2") (pinfunction "2_2") (pintype "unspecified"))
    )
    (net (code "18") (name "IN1P") (class "Default")
      (node (ref "C20") (pin "2") (pinfunction "2_2") (pintype "unspecified"))
      (node (ref "C45") (pin "2") (pinfunction "2_2") (pintype "input"))
    )
    (net (code "19") (name "INST_IN") (class "Default")
      (node (ref "K1") (pin "4") (pinfunction "4_4") (pintype "input"))
      (node (ref "K1") (pin "7") (pinfunction "7_7") (pintype "input"))
      (node (ref "U59") (pin "1") (pinfunction "1_1") (pintype "unspecified"))
    )
    (net (code "20") (name "INST_OUT") (class "Default")
      (node (ref "K1") (pin "6") (pinfunction "6_6") (pintype "input"))
      (node (ref "U59") (pin "3") (pinfunction "3_3") (pintype "unspecified"))
    )
    (net (code "21") (name "LED0") (class "Default")
      (node (ref "R49") (pin "2") (pinfunction "2_2") (pintype "input"))
      (node (ref "U60") (pin "2") (pinfunction "2_2") (pintype "unspecified"))
    )
    (net (code "22") (name "LED1") (class "Default")
      (node (ref "R48") (pin "2") (pinfunction "2_2") (pintype "input"))
      (node (ref "U60") (pin "1") (pinfunction "1_1") (pintype "unspecified"))
    )
    (net (code "23") (name "MCLK") (class "Default")
      (node (ref "R35") (pin "1") (pinfunction "1_1") (pintype "input"))
      (node (ref "U1") (pin "7") (pinfunction "GP5_SPI0CSn_I2C0SCL_UART1RX_7") (pintype "unspecified"))
    )
    (net (code "24") (name "MICBIAS") (class "Default")
      (node (ref "R53") (pin "1") (pinfunction "1_1") (pintype "input"))
      (node (ref "U42") (pin "19") (pinfunction "MICBIAS_19") (pintype "unspecified"))
    )
    (net (code "25") (name "MIDI_IN") (class "Default")
      (node (ref "R46") (pin "2") (pinfunction "2_2") (pintype "input"))
      (node (ref "U1") (pin "2") (pinfunction "GP1_SPI0CSn_I2C0SCL_UART0RX_2") (pintype "unspecified"))
      (node (ref "U63") (pin "4") (pinfunction "VO_4") (pintype "unspecified"))
    )
    (net (code "26") (name "MIDI_OUT") (class "Default")
      (node (ref "R45") (pin "2") (pinfunction "2_2") (pintype "input"))
      (node (ref "U1") (pin "1") (pinfunction "GP0_SPI0RX_I2C0SDA_UART0TX_1") (pintype "unspecified"))
    )
    (net (code "27") (name "MUX") (class "Default")
      (node (ref "U1") (pin "29") (pinfunction "GP22_29") (pintype "unspecified"))
      (node (ref "U61") (pin "10") (pinfunction "SEL2_10") (pintype "unspecified"))
      (node (ref "U61") (pin "11") (pinfunction "SEL1_11") (pintype "unspecified"))
      (node (ref "U61") (pin "9") (pinfunction "SEL3_9") (pintype "unspecified"))
    )
    (net (code "28") (name "Net-(C5-Pad2)") (class "Default")
      (node (ref "C5") (pin "2") (pinfunction "2_2") (pintype "unspecified"))
      (node (ref "R1") (pin "2") (pinfunction "2_2") (pintype "unspecified"))
    )
    (net (code "29") (name "Net-(C6-Pad2)") (class "Default")
      (node (ref "C6") (pin "2") (pinfunction "2_2") (pintype "input"))
      (node (ref "R2") (pin "1") (pinfunction "1_1") (pintype "unspecified"))
      (node (ref "U40") (pin "2") (pinfunction "2_2") (pintype "input"))
    )
    (net (code "30") (name "Net-(C8-Pad2)") (class "Default")
      (node (ref "C8") (pin "2") (pinfunction "2_2") (pintype "unspecified"))
      (node (ref "R6") (pin "2") (pinfunction "2_2") (pintype "input"))
      (node (ref "U2") (pin "1") (pinfunction "1_1") (pintype "input"))
      (node (ref "U41") (pin "2") (pinfunction "2_2") (pintype "input"))
    )
    (net (code "31") (name "Net-(C29-Pad1)") (class "Default")
      (node (ref "C29") (pin "1") (pinfunction "1_1") (pintype "input"))
      (node (ref "C32") (pin "2") (pinfunction "2_2") (pintype "unspecified"))
      (node (ref "R11") (pin "2") (pinfunction "2_2") (pintype "input"))
    )
    (net (code "32") (name "Net-(C45-Pad1)") (class "Default")
      (node (ref "C45") (pin "1") (pinfunction "1_1") (pintype "input"))
      (node (ref "C47") (pin "2") (pinfunction "2_2") (pintype "input"))
      (node (ref "R2") (pin "2") (pinfunction "2_2") (pintype "unspecified"))
    )
    (net (code "33") (name "Net-(C53-Pad2)") (class "Default")
      (node (ref "C53") (pin "2") (pinfunction "2_2") (pintype "input"))
      (node (ref "H1") (pin "1") (pinfunction "1_1") (pintype "unspecified"))
    )
    (net (code "34") (name "Net-(C54-Pad2)") (class "Default")
      (node (ref "C54") (pin "2") (pinfunction "2_2") (pintype "input"))
      (node (ref "H1") (pin "2") (pinfunction "2_2") (pintype "unspecified"))
    )
    (net (code "35") (name "Net-(D1-A)") (class "Default")
      (node (ref "D1") (pin "2") (pinfunction "A_2") (pintype "unspecified"))
      (node (ref "K1") (pin "8") (pinfunction "8_8") (pintype "input"))
      (node (ref "Q1") (pin "3") (pinfunction "C_3") (pintype "input"))
    )
    (net (code "36") (name "Net-(D2-A)") (class "Default")
      (node (ref "D2") (pin "2") (pinfunction "A_2") (pintype "unspecified"))
      (node (ref "H2") (pin "1") (pinfunction "1_1") (pintype "unspecified"))
      (node (ref "U63") (pin "2") (pinfunction "CAT_2") (pintype "unspecified"))
    )
    (net (code "37") (name "Net-(D2-K)") (class "Default")
      (node (ref "D2") (pin "1") (pinfunction "K_1") (pintype "unspecified"))
      (node (ref "R43") (pin "2") (pinfunction "2_2") (pintype "input"))
      (node (ref "U63") (pin "1") (pinfunction "AN_1") (pintype "unspecified"))
    )
    (net (code "38") (name "Net-(H2-Pad2)") (class "Default")
      (node (ref "H2") (pin "2") (pinfunction "2_2") (pintype "unspecified"))
      (node (ref "R43") (pin "1") (pinfunction "1_1") (pintype "input"))
    )
    (net (code "39") (name "Net-(H3-Pad1)") (class "Default")
      (node (ref "H3") (pin "1") (pinfunction "1_1") (pintype "unspecified"))
      (node (ref "R45") (pin "1") (pinfunction "1_1") (pintype "input"))
    )
    (net (code "40") (name "Net-(H3-Pad2)") (class "Default")
      (node (ref "H3") (pin "2") (pinfunction "2_2") (pintype "unspecified"))
      (node (ref "R44") (pin "1") (pinfunction "1_1") (pintype "input"))
    )
    (net (code "41") (name "Net-(Q1-B)") (class "Default")
      (node (ref "Q1") (pin "1") (pinfunction "B_1") (pintype "input"))
      (node (ref "R31") (pin "2") (pinfunction "2_2") (pintype "input"))
    )
    (net (code "42") (name "Net-(R4-Pad2)") (class "Default")
      (node (ref "R4") (pin "2") (pinfunction "2_2") (pintype "unspecified"))
      (node (ref "U41") (pin "1") (pinfunction "1_1") (pintype "input"))
    )
    (net (code "43") (name "Net-(U1-GP16_SPI0RX_UART0RX)") (class "Default")
      (node (ref "R49") (pin "1") (pinfunction "1_1") (pintype "input"))
      (node (ref "U1") (pin "21") (pinfunction "GP16_SPI0RX_UART0RX_21") (pintype "unspecified"))
    )
    (net (code "44") (name "Net-(U1-GP17_SPI0CSn_UART0TX)") (class "Default")
      (node (ref "R48") (pin "1") (pinfunction "1_1") (pintype "input"))
      (node (ref "U1") (pin "22") (pinfunction "GP17_SPI0CSn_UART0TX_22") (pintype "unspecified"))
    )
    (net (code "45") (name "Net-(U21-IN+)") (class "Default")
      (node (ref "R25") (pin "2") (pinfunction "2_2") (pintype "unspecified"))
      (node (ref "R26") (pin "2") (pinfunction "2_2") (pintype "unspecified"))
      (node (ref "U21") (pin "3") (pinfunction "IN+_3") (pintype "unspecified"))
    )
    (net (code "46") (name "Net-(U39A-INA+)") (class "Default")
      (node (ref "C5") (pin "1") (pinfunction "1_1") (pintype "unspecified"))
      (node (ref "R3") (pin "2") (pinfunction "2_2") (pintype "input"))
      (node (ref "U39") (pin "3") (pinfunction "INA+_3") (pintype "unspecified"))
    )
    (net (code "47") (name "Net-(U39A-INA-)") (class "Default")
      (node (ref "U39") (pin "1") (pinfunction "OUTA_1") (pintype "output"))
      (node (ref "U39") (pin "2") (pinfunction "INA-_2") (pintype "unspecified"))
      (node (ref "U40") (pin "1") (pinfunction "1_1") (pintype "input"))
    )
    (net (code "48") (name "Net-(U39B-INB+)") (class "Default")
      (node (ref "C7") (pin "2") (pinfunction "2_2") (pintype "unspecified"))
      (node (ref "R5") (pin "2") (pinfunction "2_2") (pintype "input"))
      (node (ref "U39") (pin "5") (pinfunction "INB+_5") (pintype "unspecified"))
    )
    (net (code "49") (name "Net-(U39B-INB-)") (class "Default")
      (node (ref "R4") (pin "1") (pinfunction "1_1") (pintype "unspecified"))
      (node (ref "U39") (pin "6") (pinfunction "INB-_6") (pintype "unspecified"))
      (node (ref "U39") (pin "7") (pinfunction "OUTB_7") (pintype "output"))
    )
    (net (code "50") (name "Net-(U42-AVDD)") (class "Default")
      (node (ref "C17") (pin "2") (pinfunction "2_2") (pintype "input"))
      (node (ref "U42") (pin "24") (pinfunction "AVDD_24") (pintype "unspecified"))
    )
    (net (code "51") (name "Net-(U42-BCLK)") (class "Default")
      (node (ref "R36") (pin "2") (pinfunction "2_2") (pintype "input"))
      (node (ref "U42") (pin "2") (pinfunction "BCLK_2") (pintype "unspecified"))
    )
    (net (code "52") (name "Net-(U42-DIN{slash}MFP1)") (class "Default")
      (node (ref "R38") (pin "2") (pinfunction "2_2") (pintype "input"))
      (node (ref "U42") (pin "4") (pinfunction "DIN/MFP1_4") (pintype "unspecified"))
    )
    (net (code "53") (name "Net-(U42-DOUT{slash}MFP2)") (class "Default")
      (node (ref "R39") (pin "2") (pinfunction "2_2") (pintype "input"))
      (node (ref "U42") (pin "5") (pinfunction "DOUT/MFP2_5") (pintype "unspecified"))
    )
    (net (code "54") (name "Net-(U42-DVDD)") (class "Default")
      (node (ref "C18") (pin "2") (pinfunction "2_2") (pintype "input"))
      (node (ref "U42") (pin "29") (pinfunction "DVDD_29") (pintype "unspecified"))
    )
    (net (code "55") (name "Net-(U42-GPIO{slash}MFP5)") (class "Default")
      (node (ref "TP3") (pin "1") (pinfunction "1_1") (pintype "unspecified"))
      (node (ref "U42") (pin "32") (pinfunction "GPIO/MFP5_32") (pintype "unspecified"))
    )
    (net (code "56") (name "Net-(U42-IN1_L)") (class "Default")
      (node (ref "TP10") (pin "1") (pinfunction "1_1") (pintype "unspecified"))
      (node (ref "U42") (pin "13") (pinfunction "IN1_L_13") (pintype "unspecified"))
    )
    (net (code "57") (name "Net-(U42-IN1_R)") (class "Default")
      (node (ref "TP11") (pin "1") (pinfunction "1_1") (pintype "unspecified"))
      (node (ref "U42") (pin "14") (pinfunction "IN1_R_14") (pintype "unspecified"))
    )
    (net (code "58") (name "Net-(U42-IN2_L)") (class "Default")
      (node (ref "C20") (pin "1") (pinfunction "1_1") (pintype "unspecified"))
      (node (ref "C24") (pin "2") (pinfunction "2_2") (pintype "input"))
      (node (ref "U42") (pin "15") (pinfunction "IN2_L_15") (pintype "unspecified"))
    )
    (net (code "59") (name "Net-(U42-IN2_R)") (class "Default")
      (node (ref "C48") (pin "1") (pinfunction "1_1") (pintype "unspecified"))
      (node (ref "C49") (pin "2") (pinfunction "2_2") (pintype "input"))
      (node (ref "U42") (pin "16") (pinfunction "IN2_R_16") (pintype "unspecified"))
    )
    (net (code "60") (name "Net-(U42-IN3_L)") (class "Default")
      (node (ref "TP7") (pin "1") (pinfunction "1_1") (pintype "unspecified"))
      (node (ref "U42") (pin "20") (pinfunction "IN3_L_20") (pintype "unspecified"))
    )
    (net (code "61") (name "Net-(U42-IN3_R)") (class "Default")
      (node (ref "TP6") (pin "1") (pinfunction "1_1") (pintype "unspecified"))
      (node (ref "U42") (pin "21") (pinfunction "IN3_R_21") (pintype "unspecified"))
    )
    (net (code "62") (name "Net-(U42-LOL)") (class "Default")
      (node (ref "R11") (pin "1") (pinfunction "1_1") (pintype "input"))
      (node (ref "U42") (pin "22") (pinfunction "LOL_22") (pintype "unspecified"))
    )
    (net (code "63") (name "Net-(U42-LOR)") (class "Default")
      (node (ref "TP12") (pin "1") (pinfunction "1_1") (pintype "unspecified"))
      (node (ref "U42") (pin "23") (pinfunction "LOR_23") (pintype "unspecified"))
    )
    (net (code "64") (name "Net-(U42-MCLK)") (class "Default")
      (node (ref "R35") (pin "2") (pinfunction "2_2") (pintype "input"))
      (node (ref "U42") (pin "1") (pinfunction "MCLK_1") (pintype "unspecified"))
    )
    (net (code "65") (name "Net-(U42-MISO{slash}MFP4)") (class "Default")
      (node (ref "TP2") (pin "1") (pinfunction "1_1") (pintype "unspecified"))
      (node (ref "U42") (pin "11") (pinfunction "MISO/MFP4_11") (pintype "unspecified"))
    )
    (net (code "66") (name "Net-(U42-REF)") (class "Default")
      (node (ref "C19") (pin "2") (pinfunction "2_2") (pintype "input"))
      (node (ref "C34") (pin "2") (pinfunction "2_2") (pintype "unspecified"))
      (node (ref "U42") (pin "18") (pinfunction "REF_18") (pintype "unspecified"))
    )
    (net (code "67") (name "Net-(U42-SCLK{slash}MFP3)") (class "Default")
      (node (ref "TP9") (pin "1") (pinfunction "1_1") (pintype "unspecified"))
      (node (ref "U42") (pin "8") (pinfunction "SCLK/MFP3_8") (pintype "unspecified"))
    )
    (net (code "68") (name "Net-(U42-WCLK)") (class "Default")
      (node (ref "R37") (pin "2") (pinfunction "2_2") (pintype "input"))
      (node (ref "U42") (pin "3") (pinfunction "WCLK_3") (pintype "unspecified"))
    )
    (net (code "69") (name "Net-(U64-Vin)") (class "Default")
      (node (ref "C35") (pin "2") (pinfunction "2_2") (pintype "unspecified"))
      (node (ref "L4") (pin "2") (pinfunction "2_2") (pintype "unspecified"))
      (node (ref "U64") (pin "3") (pinfunction "Vin_3") (pintype "unspecified"))
    )
    (net (code "70") (name "OUT1P") (class "Default")
      (node (ref "C32") (pin "1") (pinfunction "1_1") (pintype "unspecified"))
      (node (ref "C7") (pin "1") (pinfunction "1_1") (pintype "unspecified"))
    )
    (net (code "71") (name "POT0") (class "Default")
      (node (ref "U61") (pin "12") (pinfunction "S1A_12") (pintype "unspecified"))
      (node (ref "U62") (pin "1") (pinfunction "1_1") (pintype "unspecified"))
    )
    (net (code "72") (name "POT1") (class "Default")
      (node (ref "U61") (pin "2") (pinfunction "S2A_2") (pintype "unspecified"))
      (node (ref "U62") (pin "2") (pinfunction "2_2") (pintype "unspecified"))
    )
    (net (code "73") (name "POT2") (class "Default")
      (node (ref "U61") (pin "5") (pinfunction "S3A_5") (pintype "unspecified"))
      (node (ref "U62") (pin "3") (pinfunction "3_3") (pintype "unspecified"))
    )
    (net (code "74") (name "POT3") (class "Default")
      (node (ref "U61") (pin "13") (pinfunction "S1B_13") (pintype "unspecified"))
      (node (ref "U62") (pin "4") (pinfunction "4_4") (pintype "unspecified"))
    )
    (net (code "75") (name "POT4") (class "Default")
      (node (ref "U61") (pin "1") (pinfunction "S2B_1") (pintype "unspecified"))
      (node (ref "U62") (pin "5") (pinfunction "5_5") (pintype "unspecified"))
    )
    (net (code "76") (name "POT5") (class "Default")
      (node (ref "U61") (pin "3") (pinfunction "S3B_3") (pintype "unspecified"))
      (node (ref "U62") (pin "6") (pinfunction "6_6") (pintype "unspecified"))
    )
    (net (code "77") (name "PRE_IN") (class "Default")
      (node (ref "K1") (pin "3") (pinfunction "3_3") (pintype "input"))
      (node (ref "R1") (pin "1") (pinfunction "1_1") (pintype "unspecified"))
    )
    (net (code "78") (name "PRE_OUT") (class "Default")
      (node (ref "K1") (pin "5") (pinfunction "5_5") (pintype "input"))
      (node (ref "U2") (pin "2") (pinfunction "2_2") (pintype "input"))
    )
    (net (code "79") (name "SCL0") (class "Default")
      (node (ref "R7") (pin "2") (pinfunction "2_2") (pintype "input"))
      (node (ref "U1") (pin "27") (pinfunction "GP21_I2C0SCL_27") (pintype "unspecified"))
      (node (ref "U42") (pin "9") (pinfunction "SCL/SS#_9") (pintype "unspecified"))
    )
    (net (code "80") (name "SCL1") (class "Default")
      (node (ref "CN1") (pin "4") (pinfunction "4_4") (pintype "unspecified"))
      (node (ref "R56") (pin "2") (pinfunction "2_2") (pintype "input"))
      (node (ref "U1") (pin "5") (pinfunction "GP3_SPI0TX_I2C1SCL_5") (pintype "unspecified"))
    )
    (net (code "81") (name "SDA0") (class "Default")
      (node (ref "R40") (pin "1") (pinfunction "1_1") (pintype "input"))
      (node (ref "U1") (pin "26") (pinfunction "GP20_I2C0SDA_26") (pintype "unspecified"))
      (node (ref "U42") (pin "10") (pinfunction "SDA/MOSI_10") (pintype "unspecified"))
    )
    (net (code "82") (name "SDA1") (class "Default")
      (node (ref "CN1") (pin "3") (pinfunction "3_3") (pintype "unspecified"))
      (node (ref "R57") (pin "2") (pinfunction "2_2") (pintype "input"))
      (node (ref "U1") (pin "4") (pinfunction "GP2_SPI0SCK_I2C1SDA_4") (pintype "unspecified"))
    )
    (net (code "83") (name "SW0") (class "Default")
      (node (ref "U1") (pin "19") (pinfunction "GP14_SPI1SCK_I2C1SDA_19") (pintype "unspecified"))
      (node (ref "U60") (pin "4") (pinfunction "4_4") (pintype "unspecified"))
    )
    (net (code "84") (name "SW1") (class "Default")
      (node (ref "U1") (pin "20") (pinfunction "GP15_SPI1TX_I2C1SCL_20") (pintype "unspecified"))
      (node (ref "U60") (pin "3") (pinfunction "3_3") (pintype "unspecified"))
    )
    (net (code "85") (name "VBAT") (class "Default")
      (node (ref "C39") (pin "2") (pinfunction "2_2") (pintype "unspecified"))
      (node (ref "Q2") (pin "3") (pinfunction "D_3") (pintype "unspecified"))
      (node (ref "U55") (pin "3") (pinfunction "OUT_3") (pintype "unspecified"))
    )
    (net (code "86") (name "VBUS") (class "Default")
      (node (ref "Q2") (pin "1") (pinfunction "G_1") (pintype "unspecified"))
      (node (ref "U1") (pin "40") (pinfunction "VBUS_40") (pintype "unspecified"))
    )
    (net (code "87") (name "VIN") (class "Default")
      (node (ref "C52") (pin "2") (pinfunction "2_2") (pintype "unspecified"))
      (node (ref "U55") (pin "1") (pinfunction "IN_1") (pintype "unspecified"))
      (node (ref "U60") (pin "7") (pinfunction "7_7") (pintype "unspecified"))
    )
    (net (code "88") (name "WCLK") (class "Default")
      (node (ref "R37") (pin "1") (pinfunction "1_1") (pintype "input"))
      (node (ref "U1") (pin "10") (pinfunction "GP7_SPI0TX_I2C1SCL_10") (pintype "unspecified"))
    )
    (net (code "89") (name "unconnected-(CN1-Pad5)") (class "Default")
      (node (ref "CN1") (pin "5") (pinfunction "5_5") (pintype "unspecified+no_connect"))
    )
    (net (code "90") (name "unconnected-(CN1-Pad6)") (class "Default")
      (node (ref "CN1") (pin "6") (pinfunction "6_6") (pintype "unspecified+no_connect"))
    )
    (net (code "91") (name "unconnected-(U1-3V3_EN-Pad37)") (class "Default")
      (node (ref "U1") (pin "37") (pinfunction "3V3_EN_37") (pintype "unspecified+no_connect"))
    )
    (net (code "92") (name "unconnected-(U1-ADC_VREF-Pad35)") (class "Default")
      (node (ref "U1") (pin "35") (pinfunction "ADC_VREF_35") (pintype "unspecified+no_connect"))
    )
    (net (code "93") (name "unconnected-(U1-GP11_SPI1TX_I2C1SCL-Pad15)") (class "Default")
      (node (ref "U1") (pin "15") (pinfunction "GP11_SPI1TX_I2C1SCL_15") (pintype "unspecified+no_connect"))
    )
    (net (code "94") (name "unconnected-(U1-GP18_SPI0SCK_I2C1SDA-Pad24)") (class "Default")
      (node (ref "U1") (pin "24") (pinfunction "GP18_SPI0SCK_I2C1SDA_24") (pintype "unspecified+no_connect"))
    )
    (net (code "95") (name "unconnected-(U1-GP19_SPI0TX_I2C1SCL-Pad25)") (class "Default")
      (node (ref "U1") (pin "25") (pinfunction "GP19_SPI0TX_I2C1SCL_25") (pintype "unspecified+no_connect"))
    )
    (net (code "96") (name "unconnected-(U1-PadTP1)") (class "Default")
      (node (ref "U1") (pin "TP1") (pinfunction "TP1_TP1") (pintype "unspecified+no_connect"))
    )
    (net (code "97") (name "unconnected-(U1-PadTP2)") (class "Default")
      (node (ref "U1") (pin "TP2") (pinfunction "TP2_TP2") (pintype "unspecified+no_connect"))
    )
    (net (code "98") (name "unconnected-(U1-PadTP3)") (class "Default")
      (node (ref "U1") (pin "TP3") (pinfunction "TP3_TP3") (pintype "unspecified+no_connect"))
    )
    (net (code "99") (name "unconnected-(U1-PadTP4)") (class "Default")
      (node (ref "U1") (pin "TP4") (pinfunction "TP4_TP4") (pintype "unspecified+no_connect"))
    )
    (net (code "100") (name "unconnected-(U1-PadTP5)") (class "Default")
      (node (ref "U1") (pin "TP5") (pinfunction "TP5_TP5") (pintype "unspecified+no_connect"))
    )
    (net (code "101") (name "unconnected-(U1-PadTP6)") (class "Default")
      (node (ref "U1") (pin "TP6") (pinfunction "TP6_TP6") (pintype "unspecified+no_connect"))
    )
    (net (code "102") (name "unconnected-(U1-RUN-Pad30)") (class "Default")
      (node (ref "U1") (pin "30") (pinfunction "RUN_30") (pintype "unspecified"))
    )
    (net (code "103") (name "unconnected-(U1-SWCLK-Pad43)") (class "Default")
      (node (ref "U1") (pin "43") (pinfunction "SWCLK_43") (pintype "unspecified+no_connect"))
    )
    (net (code "104") (name "unconnected-(U1-SWDIO-Pad41)") (class "Default")
      (node (ref "U1") (pin "41") (pinfunction "SWDIO_41") (pintype "unspecified+no_connect"))
    )
    (net (code "105") (name "unconnected-(U63-NC-Pad3)") (class "Default")
      (node (ref "U63") (pin "3") (pinfunction "NC_3") (pintype "unspecified+no_connect"))
    )
    (net (code "106") (name "~BYPASS") (class "Default")
      (node (ref "R31") (pin "1") (pinfunction "1_1") (pintype "input"))
      (node (ref "R34") (pin "2") (pinfunction "2_2") (pintype "input"))
      (node (ref "U1") (pin "14") (pinfunction "GP10_SPI1SCK_I2C1SDA_14") (pintype "unspecified"))
    )
    (net (code "107") (name "~RESET") (class "Default")
      (node (ref "R12") (pin "2") (pinfunction "2_2") (pintype "input"))
      (node (ref "U1") (pin "6") (pinfunction "GP4_SPI0RX_I2C0SDA_UART1TX_6") (pintype "unspecified"))
      (node (ref "U42") (pin "31") (pinfunction "RESET#_31") (pintype "unspecified"))
    )
  )
)
